# Oscilloscope.net
KiCad netlist of a schematic drawn in Altium Designer
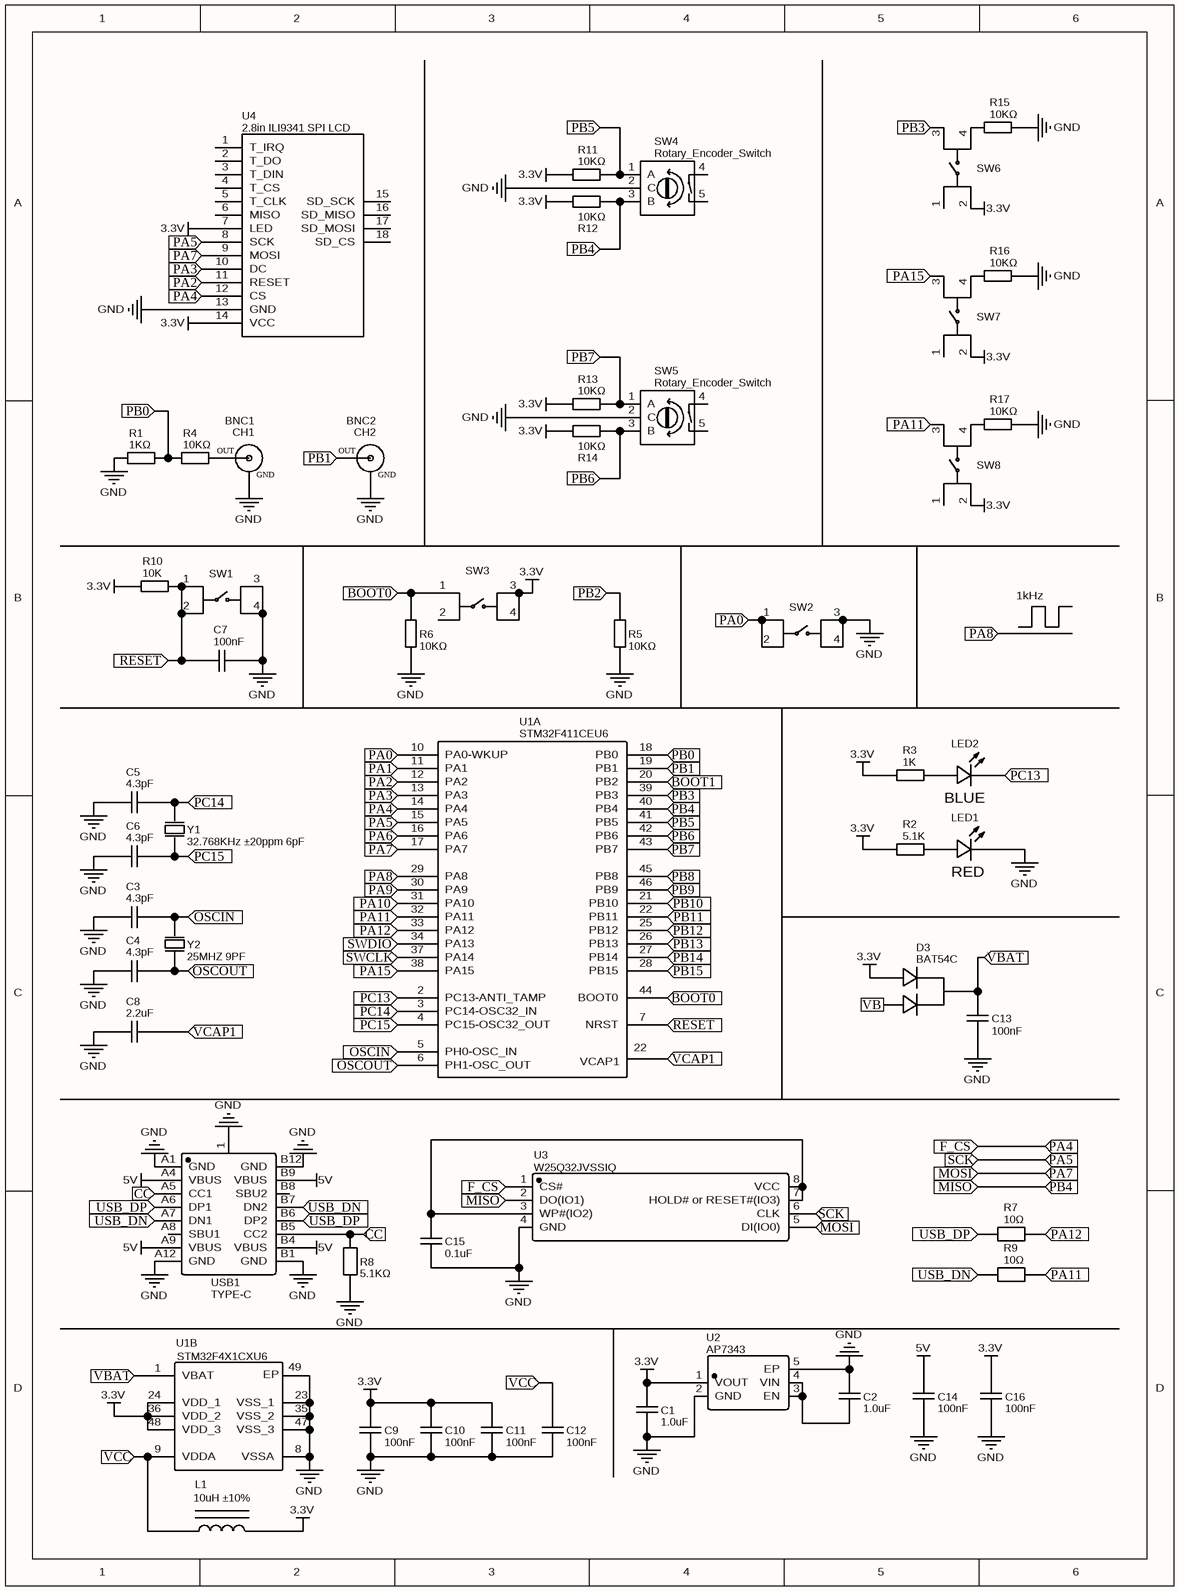
[diagram p0: Oscilloscope.schdoc]

(export (version "E")
  (design (tool "Eeschema 10.0.6"))
  (components
    (comp (ref "BNC1")
      (value "CH1")
      (fields (field (name "CONTRIBUTOR") "SparkFun"))
      (libsource (lib "altium-import") (part "root_0_CH1_"))
    )
    (comp (ref "BNC2")
      (value "CH2")
      (fields (field (name "CONTRIBUTOR") "SparkFun"))
      (libsource (lib "altium-import") (part "root_0_CH2_"))
    )
    (comp (ref "C1")
      (value "1.0uF")
      (fields (field (name "CONTRIBUTOR") "LCEDA_Lib"))
      (libsource (lib "altium-import") (part "root_3_1.0uF_"))
    )
    (comp (ref "C2")
      (value "1.0uF")
      (fields (field (name "CONTRIBUTOR") "LCEDA_Lib"))
      (libsource (lib "altium-import") (part "root_3_1.0uF_"))
    )
    (comp (ref "C3")
      (value "4.3pF")
      (fields (field (name "CONTRIBUTOR") "LCEDA_Lib"))
      (libsource (lib "altium-import") (part "root_0_4.3pF_"))
    )
    (comp (ref "C4")
      (value "4.3pF")
      (fields (field (name "CONTRIBUTOR") "LCEDA_Lib"))
      (libsource (lib "altium-import") (part "root_0_4.3pF_"))
    )
    (comp (ref "C5")
      (value "4.3pF")
      (fields (field (name "CONTRIBUTOR") "LCEDA_Lib"))
      (libsource (lib "altium-import") (part "root_0_4.3pF_"))
    )
    (comp (ref "C6")
      (value "4.3pF")
      (fields (field (name "CONTRIBUTOR") "LCEDA_Lib"))
      (libsource (lib "altium-import") (part "root_0_4.3pF_"))
    )
    (comp (ref "C7")
      (value "100nF")
      (fields (field (name "MANUFACTURER PART") "CL10A105KO8NNNC") (field (name "MANUFACTURER") "SAMSUNG"))
      (libsource (lib "altium-import") (part "root_0_100nF_"))
    )
    (comp (ref "C8")
      (value "2.2uF")
      (fields (field (name "CONTRIBUTOR") "LCEDA_Lib"))
      (libsource (lib "altium-import") (part "root_0_2.2uF_"))
    )
    (comp (ref "C9")
      (value "100nF")
      (fields (field (name "CONTRIBUTOR") "LCEDA_Lib"))
      (libsource (lib "altium-import") (part "root_3_100nF_"))
    )
    (comp (ref "C10")
      (value "100nF")
      (fields (field (name "CONTRIBUTOR") "LCEDA_Lib"))
      (libsource (lib "altium-import") (part "root_3_100nF_"))
    )
    (comp (ref "C11")
      (value "100nF")
      (fields (field (name "CONTRIBUTOR") "LCEDA_Lib"))
      (libsource (lib "altium-import") (part "root_3_100nF_"))
    )
    (comp (ref "C12")
      (value "100nF")
      (fields (field (name "CONTRIBUTOR") "LCEDA_Lib"))
      (libsource (lib "altium-import") (part "root_3_100nF_"))
    )
    (comp (ref "C13")
      (value "100nF")
      (fields (field (name "CONTRIBUTOR") "LCEDA_Lib"))
      (libsource (lib "altium-import") (part "root_3_100nF_"))
    )
    (comp (ref "C14")
      (value "100nF")
      (fields (field (name "CONTRIBUTOR") "LCEDA_Lib"))
      (libsource (lib "altium-import") (part "root_3_100nF_"))
    )
    (comp (ref "C15")
      (value "0.1uF")
      (fields (field (name "CONTRIBUTOR") "LCEDA_Lib"))
      (libsource (lib "altium-import") (part "root_3_0.1uF_"))
    )
    (comp (ref "C16")
      (value "100nF")
      (fields (field (name "CONTRIBUTOR") "LCEDA_Lib"))
      (libsource (lib "altium-import") (part "root_3_100nF_"))
    )
    (comp (ref "D3")
      (value "BAT54C")
      (fields (field (name "MANUFACTURER") "CJ(江苏长电/长晶)"))
      (libsource (lib "altium-import") (part "root_0_BAT54C_"))
    )
    (comp (ref "L1")
      (value "10uH ±10%")
      (fields (field (name "CONTRIBUTOR") "LCEDA_Lib"))
      (libsource (lib "altium-import") (part "root_0_10uH ±10%_"))
    )
    (comp (ref "LED1")
      (value "XL-0603QYGC")
      (fields (field (name "MANUFACTURER") "KENTO"))
      (libsource (lib "altium-import") (part "root_0_XL-0603QYGC_"))
    )
    (comp (ref "LED2")
      (value "XL-0603QYGC")
      (fields (field (name "MANUFACTURER") "KENTO"))
      (libsource (lib "altium-import") (part "root_0_XL-0603QYGC_"))
    )
    (comp (ref "R1")
      (value "1KΩ")
      (fields (field (name "MANUFACTURER") "YAGEO") (field (name "MANUFACTURER PART") "RC0603FR-07510RL"))
      (libsource (lib "altium-import") (part "root_0_1KΩ_"))
    )
    (comp (ref "R2")
      (value "5.1K")
      (fields (field (name "MANUFACTURER") "YAGEO") (field (name "MANUFACTURER PART") "RC0603FR-07510RL"))
      (libsource (lib "altium-import") (part "root_0_5.1K_"))
    )
    (comp (ref "R3")
      (value "1K")
      (fields (field (name "MANUFACTURER") "YAGEO") (field (name "MANUFACTURER PART") "RC0603FR-07510RL"))
      (libsource (lib "altium-import") (part "root_0_1K_"))
    )
    (comp (ref "R4")
      (value "10KΩ")
      (fields (field (name "MANUFACTURER") "YAGEO") (field (name "MANUFACTURER PART") "RC0603FR-07510RL"))
      (libsource (lib "altium-import") (part "root_0_10KΩ_"))
    )
    (comp (ref "R5")
      (value "10KΩ")
      (fields (field (name "MANUFACTURER") "YAGEO") (field (name "MANUFACTURER PART") "RC0603FR-07510RL"))
      (libsource (lib "altium-import") (part "root_1_10KΩ_"))
    )
    (comp (ref "R6")
      (value "10KΩ")
      (fields (field (name "MANUFACTURER") "YAGEO") (field (name "MANUFACTURER PART") "RC0603FR-07510RL"))
      (libsource (lib "altium-import") (part "root_1_10KΩ_"))
    )
    (comp (ref "R7")
      (value "10Ω")
      (fields (field (name "CONTRIBUTOR") "LCEDA_Lib"))
      (libsource (lib "altium-import") (part "root_0_10Ω_"))
    )
    (comp (ref "R8")
      (value "5.1KΩ")
      (fields (field (name "CONTRIBUTOR") "LCEDA_Lib"))
      (libsource (lib "altium-import") (part "root_3_5.1KΩ_"))
    )
    (comp (ref "R9")
      (value "10Ω")
      (fields (field (name "CONTRIBUTOR") "LCEDA_Lib"))
      (libsource (lib "altium-import") (part "root_0_10Ω_"))
    )
    (comp (ref "R10")
      (value "10K")
      (fields (field (name "MANUFACTURER") "YAGEO") (field (name "MANUFACTURER PART") "RC0603JR-0710KL"))
      (libsource (lib "altium-import") (part "root_2_10K_"))
    )
    (comp (ref "R11")
      (value "10KΩ")
      (fields (field (name "MANUFACTURER") "YAGEO") (field (name "MANUFACTURER PART") "RC0603FR-07510RL"))
      (libsource (lib "altium-import") (part "root_2_10KΩ_"))
    )
    (comp (ref "R12")
      (value "10KΩ")
      (fields (field (name "MANUFACTURER") "YAGEO") (field (name "MANUFACTURER PART") "RC0603FR-07510RL"))
      (libsource (lib "altium-import") (part "root_2_10KΩ_"))
    )
    (comp (ref "R13")
      (value "10KΩ")
      (fields (field (name "MANUFACTURER") "YAGEO") (field (name "MANUFACTURER PART") "RC0603FR-07510RL"))
      (libsource (lib "altium-import") (part "root_2_10KΩ_"))
    )
    (comp (ref "R14")
      (value "10KΩ")
      (fields (field (name "MANUFACTURER") "YAGEO") (field (name "MANUFACTURER PART") "RC0603FR-07510RL"))
      (libsource (lib "altium-import") (part "root_2_10KΩ_"))
    )
    (comp (ref "R15")
      (value "10KΩ")
      (fields (field (name "MANUFACTURER") "YAGEO") (field (name "MANUFACTURER PART") "RC0603FR-07510RL"))
      (libsource (lib "altium-import") (part "root_2_10KΩ_"))
    )
    (comp (ref "R16")
      (value "10KΩ")
      (fields (field (name "MANUFACTURER") "YAGEO") (field (name "MANUFACTURER PART") "RC0603FR-07510RL"))
      (libsource (lib "altium-import") (part "root_2_10KΩ_"))
    )
    (comp (ref "R17")
      (value "10KΩ")
      (fields (field (name "MANUFACTURER") "YAGEO") (field (name "MANUFACTURER PART") "RC0603FR-07510RL"))
      (libsource (lib "altium-import") (part "root_2_10KΩ_"))
    )
    (comp (ref "SW1")
      (value "K2-6639SP-C4SC-04")
      (fields (field (name "MANUFACTURER") "HRO"))
      (libsource (lib "altium-import") (part "root_0_K2-6639SP-C4SC-04_"))
    )
    (comp (ref "SW2")
      (value "K2-6639SP-C4SC-04")
      (fields (field (name "MANUFACTURER") "HRO"))
      (libsource (lib "altium-import") (part "root_0_K2-6639SP-C4SC-04_"))
    )
    (comp (ref "SW3")
      (value "K2-6639SP-C4SC-04")
      (fields (field (name "MANUFACTURER") "HRO"))
      (libsource (lib "altium-import") (part "root_0_K2-6639SP-C4SC-04_"))
    )
    (comp (ref "SW4")
      (value "Rotary_Encoder_Switch")
      (fields (field (name "CONTRIBUTOR") "vosemvosemsot"))
      (libsource (lib "altium-import") (part "root_0_Rotary_Encoder_Switch_"))
    )
    (comp (ref "SW5")
      (value "Rotary_Encoder_Switch")
      (fields (field (name "CONTRIBUTOR") "vosemvosemsot"))
      (libsource (lib "altium-import") (part "root_0_Rotary_Encoder_Switch_"))
    )
    (comp (ref "SW6")
      (value "K2-6639SP-C4SC-04")
      (fields (field (name "MANUFACTURER") "HRO"))
      (libsource (lib "altium-import") (part "root_1_K2-6639SP-C4SC-04_"))
    )
    (comp (ref "SW7")
      (value "K2-6639SP-C4SC-04")
      (fields (field (name "MANUFACTURER") "HRO"))
      (libsource (lib "altium-import") (part "root_1_K2-6639SP-C4SC-04_"))
    )
    (comp (ref "SW8")
      (value "K2-6639SP-C4SC-04")
      (fields (field (name "MANUFACTURER") "HRO"))
      (libsource (lib "altium-import") (part "root_1_K2-6639SP-C4SC-04_"))
    )
    (comp (ref "U1A")
      (value "STM32F411CEU6")
      (fields
        (field (name "MANUFACTURER") "ST")
        (field (name "MANUFACTURER PART") "STM32F103C8T6")
        (field (name "SUBPART_NO") "1")
      )
      (libsource (lib "altium-import") (part "root_0_STM32F411CEU6_"))
    )
    (comp (ref "U1B")
      (value "STM32F4X1CXU6")
      (fields
        (field (name "MANUFACTURER") "ST")
        (field (name "MANUFACTURER PART") "STM32F103C8T6")
        (field (name "SUBPART_NO") "2")
      )
      (libsource (lib "altium-import") (part "root_0_STM32F4X1CXU6_"))
    )
    (comp (ref "U2")
      (value "AP7343")
      (fields
        (field (name "MANUFACTURER") "DIODES(美台)")
        (field (name "MANUFACTURER PART") "AP7343D-22FS4-7B")
        (field (name "CONTRIBUTOR") "LCSC")
      )
      (libsource (lib "altium-import") (part "root_0_AP7343_"))
    )
    (comp (ref "U3")
      (value "W25Q32JVSSIQ")
      (fields (field (name "MANUFACTURER") "WINBOND(华邦)") (field (name "CONTRIBUTOR") "LCSC"))
      (libsource (lib "altium-import") (part "root_0_W25Q32JVSSIQ_"))
    )
    (comp (ref "U4")
      (value "2.8in ILI9341 SPI LCD")
      (fields (field (name "CONTRIBUTOR") "ananya0211"))
      (libsource (lib "altium-import") (part "root_0_2.8in ILI9341 SPI LCD_"))
    )
    (comp (ref "USB1")
      (value "TYPE-C")
      (fields
        (field (name "MANUFACTURER") "CIKI(皓富)")
        (field (name "MANUFACTURER PART") "TYPE-C-2.0-16PIN-SMT-3")
        (field (name "CONTRIBUTOR") "lcsc")
      )
      (libsource (lib "altium-import") (part "root_0_TYPE-C_"))
    )
    (comp (ref "Y1")
      (value "32.768KHz ±20ppm 6pF")
      (fields (field (name "MANUFACTURER") "YXC") (field (name "MANUFACTURER PART") "X49SD8MSD2SC"))
      (libsource (lib "altium-import") (part "root_1_32.768KHz ±20ppm 6pF_"))
    )
    (comp (ref "Y2")
      (value "25MHZ 9PF")
      (fields (field (name "MANUFACTURER") "YXC") (field (name "MANUFACTURER PART") "X49SD8MSD2SC"))
      (libsource (lib "altium-import") (part "root_1_25MHZ 9PF_"))
    )
  )
  (nets
    (net (code "1") (name "/BOOT0") (class "Default")
      (node (ref "R6") (pin "2") (pinfunction "2_2") (pintype "passive"))
      (node (ref "SW3") (pin "1") (pinfunction "1_1") (pintype "passive"))
      (node (ref "U1A") (pin "44") (pinfunction "BOOT0_44") (pintype "passive"))
    )
    (net (code "2") (name "/BOOT1") (class "Default")
      (node (ref "U1A") (pin "20") (pinfunction "PB2_20") (pintype "passive"))
    )
    (net (code "3") (name "/CC") (class "Default")
      (node (ref "R8") (pin "1") (pinfunction "1_1") (pintype "passive"))
      (node (ref "USB1") (pin "A5") (pinfunction "CC1_A5") (pintype "passive"))
      (node (ref "USB1") (pin "B5") (pinfunction "CC2_B5") (pintype "passive"))
    )
    (net (code "4") (name "/F_CS") (class "Default")
      (node (ref "U1A") (pin "14") (pinfunction "PA4_14") (pintype "passive"))
      (node (ref "U3") (pin "1") (pinfunction "CS#_1") (pintype "passive"))
      (node (ref "U4") (pin "12") (pinfunction "CS_12") (pintype "passive"))
    )
    (net (code "5") (name "/MISO") (class "Default")
      (node (ref "R12") (pin "1") (pinfunction "1_1") (pintype "passive"))
      (node (ref "SW4") (pin "3") (pinfunction "B_3") (pintype "passive"))
      (node (ref "U1A") (pin "40") (pinfunction "PB4_40") (pintype "passive"))
      (node (ref "U3") (pin "2") (pinfunction "DO(IO1)_2") (pintype "passive"))
    )
    (net (code "6") (name "/MOSI") (class "Default")
      (node (ref "U1A") (pin "17") (pinfunction "PA7_17") (pintype "passive"))
      (node (ref "U3") (pin "5") (pinfunction "DI(IO0)_5") (pintype "passive"))
      (node (ref "U4") (pin "9") (pinfunction "MOSI_9") (pintype "passive"))
    )
    (net (code "7") (name "/OSCIN") (class "Default")
      (node (ref "C3") (pin "2") (pinfunction "2_2") (pintype "passive"))
      (node (ref "U1A") (pin "5") (pinfunction "PH0-OSC_IN_5") (pintype "passive"))
      (node (ref "Y2") (pin "1") (pinfunction "OSC1_1") (pintype "passive"))
    )
    (net (code "8") (name "/OSCOUT") (class "Default")
      (node (ref "C4") (pin "2") (pinfunction "2_2") (pintype "passive"))
      (node (ref "U1A") (pin "6") (pinfunction "PH1-OSC_OUT_6") (pintype "passive"))
      (node (ref "Y2") (pin "2") (pinfunction "OSC2_2") (pintype "passive"))
    )
    (net (code "9") (name "/PA0") (class "Default")
      (node (ref "SW2") (pin "1") (pinfunction "1_1") (pintype "passive"))
      (node (ref "SW2") (pin "2") (pinfunction "2_2") (pintype "passive"))
      (node (ref "U1A") (pin "10") (pinfunction "PA0-WKUP_10") (pintype "passive"))
    )
    (net (code "10") (name "/PA1") (class "Default")
      (node (ref "U1A") (pin "11") (pinfunction "PA1_11") (pintype "passive"))
    )
    (net (code "11") (name "/PA2") (class "Default")
      (node (ref "U1A") (pin "12") (pinfunction "PA2_12") (pintype "passive"))
      (node (ref "U4") (pin "11") (pinfunction "RESET_11") (pintype "passive"))
    )
    (net (code "12") (name "/PA3") (class "Default")
      (node (ref "U1A") (pin "13") (pinfunction "PA3_13") (pintype "passive"))
      (node (ref "U4") (pin "10") (pinfunction "DC_10") (pintype "passive"))
    )
    (net (code "13") (name "/PA5") (class "Default")
      (node (ref "U1A") (pin "15") (pinfunction "PA5_15") (pintype "passive"))
      (node (ref "U3") (pin "6") (pinfunction "CLK_6") (pintype "passive"))
      (node (ref "U4") (pin "8") (pinfunction "SCK_8") (pintype "passive"))
    )
    (net (code "14") (name "/PA6") (class "Default")
      (node (ref "U1A") (pin "16") (pinfunction "PA6_16") (pintype "passive"))
    )
    (net (code "15") (name "/PA8") (class "Default")
      (node (ref "U1A") (pin "29") (pinfunction "PA8_29") (pintype "passive"))
    )
    (net (code "16") (name "/PA9") (class "Default")
      (node (ref "U1A") (pin "30") (pinfunction "PA9_30") (pintype "passive"))
    )
    (net (code "17") (name "/PA10") (class "Default")
      (node (ref "U1A") (pin "31") (pinfunction "PA10_31") (pintype "passive"))
    )
    (net (code "18") (name "/PA11") (class "Default")
      (node (ref "R9") (pin "2") (pinfunction "2_2") (pintype "passive"))
      (node (ref "SW8") (pin "3") (pinfunction "3_3") (pintype "passive"))
      (node (ref "U1A") (pin "32") (pinfunction "PA11_32") (pintype "passive"))
    )
    (net (code "19") (name "/PA12") (class "Default")
      (node (ref "R7") (pin "2") (pinfunction "2_2") (pintype "passive"))
      (node (ref "U1A") (pin "33") (pinfunction "PA12_33") (pintype "passive"))
    )
    (net (code "20") (name "/PA15") (class "Default")
      (node (ref "SW7") (pin "3") (pinfunction "3_3") (pintype "passive"))
      (node (ref "U1A") (pin "38") (pinfunction "PA15_38") (pintype "passive"))
    )
    (net (code "21") (name "/PB0") (class "Default")
      (node (ref "R1") (pin "2") (pinfunction "2_2") (pintype "passive"))
      (node (ref "R4") (pin "1") (pinfunction "1_1") (pintype "passive"))
      (node (ref "U1A") (pin "18") (pinfunction "PB0_18") (pintype "passive"))
    )
    (net (code "22") (name "/PB1") (class "Default")
      (node (ref "BNC2") (pin "S") (pinfunction "OUT_S") (pintype "passive"))
      (node (ref "U1A") (pin "19") (pinfunction "PB1_19") (pintype "passive"))
    )
    (net (code "23") (name "/PB2") (class "Default")
      (node (ref "R5") (pin "2") (pinfunction "2_2") (pintype "passive"))
    )
    (net (code "24") (name "/PB3") (class "Default")
      (node (ref "SW6") (pin "3") (pinfunction "3_3") (pintype "passive"))
      (node (ref "U1A") (pin "39") (pinfunction "PB3_39") (pintype "passive"))
    )
    (net (code "25") (name "/PB5") (class "Default")
      (node (ref "R11") (pin "1") (pinfunction "1_1") (pintype "passive"))
      (node (ref "SW4") (pin "1") (pinfunction "A_1") (pintype "passive"))
      (node (ref "U1A") (pin "41") (pinfunction "PB5_41") (pintype "passive"))
    )
    (net (code "26") (name "/PB6") (class "Default")
      (node (ref "R14") (pin "1") (pinfunction "1_1") (pintype "passive"))
      (node (ref "SW5") (pin "3") (pinfunction "B_3") (pintype "passive"))
      (node (ref "U1A") (pin "42") (pinfunction "PB6_42") (pintype "passive"))
    )
    (net (code "27") (name "/PB7") (class "Default")
      (node (ref "R13") (pin "1") (pinfunction "1_1") (pintype "passive"))
      (node (ref "SW5") (pin "1") (pinfunction "A_1") (pintype "passive"))
      (node (ref "U1A") (pin "43") (pinfunction "PB7_43") (pintype "passive"))
    )
    (net (code "28") (name "/PB8") (class "Default")
      (node (ref "U1A") (pin "45") (pinfunction "PB8_45") (pintype "passive"))
    )
    (net (code "29") (name "/PB9") (class "Default")
      (node (ref "U1A") (pin "46") (pinfunction "PB9_46") (pintype "passive"))
    )
    (net (code "30") (name "/PB10") (class "Default")
      (node (ref "U1A") (pin "21") (pinfunction "PB10_21") (pintype "passive"))
    )
    (net (code "31") (name "/PB11") (class "Default")
      (node (ref "U1A") (pin "22") (pinfunction "PB11_22") (pintype "passive"))
    )
    (net (code "32") (name "/PB12") (class "Default")
      (node (ref "U1A") (pin "25") (pinfunction "PB12_25") (pintype "passive"))
    )
    (net (code "33") (name "/PB13") (class "Default")
      (node (ref "U1A") (pin "26") (pinfunction "PB13_26") (pintype "passive"))
    )
    (net (code "34") (name "/PB14") (class "Default")
      (node (ref "U1A") (pin "27") (pinfunction "PB14_27") (pintype "passive"))
    )
    (net (code "35") (name "/PB15") (class "Default")
      (node (ref "U1A") (pin "28") (pinfunction "PB15_28") (pintype "passive"))
    )
    (net (code "36") (name "/PC13") (class "Default")
      (node (ref "LED2") (pin "2") (pinfunction "K_2") (pintype "passive"))
      (node (ref "U1A") (pin "2") (pinfunction "PC13-ANTI_TAMP_2") (pintype "passive"))
    )
    (net (code "37") (name "/PC14") (class "Default")
      (node (ref "C5") (pin "2") (pinfunction "2_2") (pintype "passive"))
      (node (ref "U1A") (pin "3") (pinfunction "PC14-OSC32_IN_3") (pintype "passive"))
      (node (ref "Y1") (pin "1") (pinfunction "OSC1_1") (pintype "passive"))
    )
    (net (code "38") (name "/PC15") (class "Default")
      (node (ref "C6") (pin "2") (pinfunction "2_2") (pintype "passive"))
      (node (ref "U1A") (pin "4") (pinfunction "PC15-OSC32_OUT_4") (pintype "passive"))
      (node (ref "Y1") (pin "2") (pinfunction "OSC2_2") (pintype "passive"))
    )
    (net (code "39") (name "/RESET") (class "Default")
      (node (ref "C7") (pin "1") (pinfunction "1_1") (pintype "passive"))
      (node (ref "R10") (pin "1") (pinfunction "1_1") (pintype "passive"))
      (node (ref "SW1") (pin "1") (pinfunction "1_1") (pintype "passive"))
      (node (ref "SW1") (pin "2") (pinfunction "2_2") (pintype "passive"))
      (node (ref "U1A") (pin "7") (pinfunction "NRST_7") (pintype "passive"))
    )
    (net (code "40") (name "/SWCLK") (class "Default")
      (node (ref "U1A") (pin "37") (pinfunction "PA14_37") (pintype "passive"))
    )
    (net (code "41") (name "/SWDIO") (class "Default")
      (node (ref "U1A") (pin "34") (pinfunction "PA13_34") (pintype "passive"))
    )
    (net (code "42") (name "/USB_DN") (class "Default")
      (node (ref "R9") (pin "1") (pinfunction "1_1") (pintype "passive"))
      (node (ref "USB1") (pin "A7") (pinfunction "DN1_A7") (pintype "passive"))
      (node (ref "USB1") (pin "B7") (pinfunction "DN2_B7") (pintype "passive"))
    )
    (net (code "43") (name "/USB_DP") (class "Default")
      (node (ref "R7") (pin "1") (pinfunction "1_1") (pintype "passive"))
      (node (ref "USB1") (pin "A6") (pinfunction "DP1_A6") (pintype "passive"))
      (node (ref "USB1") (pin "B6") (pinfunction "DP2_B6") (pintype "passive"))
    )
    (net (code "44") (name "/VB") (class "Default")
      (node (ref "D3") (pin "2") (pinfunction "A2_2") (pintype "passive"))
    )
    (net (code "45") (name "/VBAT") (class "Default")
      (node (ref "C13") (pin "1") (pinfunction "1_1") (pintype "passive"))
      (node (ref "D3") (pin "3") (pinfunction "K_3") (pintype "passive"))
      (node (ref "U1B") (pin "1") (pinfunction "VBAT_1") (pintype "passive"))
    )
    (net (code "46") (name "/VCAP1") (class "Default")
      (node (ref "C8") (pin "2") (pinfunction "2_2") (pintype "passive"))
    )
    (net (code "47") (name "/VCC") (class "Default")
      (node (ref "C12") (pin "1") (pinfunction "1_1") (pintype "passive"))
      (node (ref "L1") (pin "1") (pinfunction "1_1") (pintype "passive"))
      (node (ref "U1B") (pin "9") (pinfunction "VDDA_9") (pintype "passive"))
    )
    (net (code "48") (name "3.3V") (class "Default")
      (node (ref "C1") (pin "1") (pinfunction "1_1") (pintype "passive"))
      (node (ref "C10") (pin "1") (pinfunction "1_1") (pintype "passive"))
      (node (ref "C11") (pin "1") (pinfunction "1_1") (pintype "passive"))
      (node (ref "C16") (pin "1") (pinfunction "1_1") (pintype "passive"))
      (node (ref "C9") (pin "1") (pinfunction "1_1") (pintype "passive"))
      (node (ref "D3") (pin "1") (pinfunction "A1_1") (pintype "passive"))
      (node (ref "L1") (pin "2") (pinfunction "2_2") (pintype "passive"))
      (node (ref "R10") (pin "2") (pinfunction "2_2") (pintype "passive"))
      (node (ref "R11") (pin "2") (pinfunction "2_2") (pintype "passive"))
      (node (ref "R12") (pin "2") (pinfunction "2_2") (pintype "passive"))
      (node (ref "R13") (pin "2") (pinfunction "2_2") (pintype "passive"))
      (node (ref "R14") (pin "2") (pinfunction "2_2") (pintype "passive"))
      (node (ref "R2") (pin "1") (pinfunction "1_1") (pintype "passive"))
      (node (ref "R3") (pin "1") (pinfunction "1_1") (pintype "passive"))
      (node (ref "SW3") (pin "3") (pinfunction "3_3") (pintype "passive"))
      (node (ref "SW3") (pin "4") (pinfunction "4_4") (pintype "passive"))
      (node (ref "SW6") (pin "2") (pinfunction "2_2") (pintype "passive"))
      (node (ref "SW7") (pin "2") (pinfunction "2_2") (pintype "passive"))
      (node (ref "SW8") (pin "2") (pinfunction "2_2") (pintype "passive"))
      (node (ref "U1B") (pin "24") (pinfunction "VDD_1_24") (pintype "passive"))
      (node (ref "U1B") (pin "36") (pinfunction "VDD_2_36") (pintype "passive"))
      (node (ref "U1B") (pin "48") (pinfunction "VDD_3_48") (pintype "passive"))
      (node (ref "U2") (pin "1") (pinfunction "VOUT_1") (pintype "passive"))
      (node (ref "U4") (pin "14") (pinfunction "VCC_14") (pintype "passive"))
      (node (ref "U4") (pin "7") (pinfunction "LED_7") (pintype "passive"))
    )
    (net (code "49") (name "5V") (class "Default")
      (node (ref "C14") (pin "1") (pinfunction "1_1") (pintype "passive"))
      (node (ref "USB1") (pin "A4") (pinfunction "VBUS_A4") (pintype "passive"))
      (node (ref "USB1") (pin "A9") (pinfunction "VBUS_A9") (pintype "passive"))
      (node (ref "USB1") (pin "B4") (pinfunction "VBUS_B4") (pintype "passive"))
      (node (ref "USB1") (pin "B9") (pinfunction "VBUS_B9") (pintype "passive"))
    )
    (net (code "50") (name "GND") (class "Default")
      (node (ref "BNC1") (pin "GND") (pinfunction "GND_GND") (pintype "passive"))
      (node (ref "BNC2") (pin "GND") (pinfunction "GND_GND") (pintype "passive"))
      (node (ref "C1") (pin "2") (pinfunction "2_2") (pintype "passive"))
      (node (ref "C10") (pin "2") (pinfunction "2_2") (pintype "passive"))
      (node (ref "C11") (pin "2") (pinfunction "2_2") (pintype "passive"))
      (node (ref "C12") (pin "2") (pinfunction "2_2") (pintype "passive"))
      (node (ref "C13") (pin "2") (pinfunction "2_2") (pintype "passive"))
      (node (ref "C14") (pin "2") (pinfunction "2_2") (pintype "passive"))
      (node (ref "C15") (pin "2") (pinfunction "2_2") (pintype "passive"))
      (node (ref "C16") (pin "2") (pinfunction "2_2") (pintype "passive"))
      (node (ref "C2") (pin "1") (pinfunction "1_1") (pintype "passive"))
      (node (ref "C3") (pin "1") (pinfunction "1_1") (pintype "passive"))
      (node (ref "C4") (pin "1") (pinfunction "1_1") (pintype "passive"))
      (node (ref "C5") (pin "1") (pinfunction "1_1") (pintype "passive"))
      (node (ref "C6") (pin "1") (pinfunction "1_1") (pintype "passive"))
      (node (ref "C7") (pin "2") (pinfunction "2_2") (pintype "passive"))
      (node (ref "C8") (pin "1") (pinfunction "1_1") (pintype "passive"))
      (node (ref "C9") (pin "2") (pinfunction "2_2") (pintype "passive"))
      (node (ref "LED1") (pin "2") (pinfunction "K_2") (pintype "passive"))
      (node (ref "R1") (pin "1") (pinfunction "1_1") (pintype "passive"))
      (node (ref "R15") (pin "1") (pinfunction "1_1") (pintype "passive"))
      (node (ref "R16") (pin "1") (pinfunction "1_1") (pintype "passive"))
      (node (ref "R17") (pin "1") (pinfunction "1_1") (pintype "passive"))
      (node (ref "R5") (pin "1") (pinfunction "1_1") (pintype "passive"))
      (node (ref "R6") (pin "1") (pinfunction "1_1") (pintype "passive"))
      (node (ref "R8") (pin "2") (pinfunction "2_2") (pintype "passive"))
      (node (ref "SW1") (pin "3") (pinfunction "3_3") (pintype "passive"))
      (node (ref "SW1") (pin "4") (pinfunction "4_4") (pintype "passive"))
      (node (ref "SW2") (pin "3") (pinfunction "3_3") (pintype "passive"))
      (node (ref "SW2") (pin "4") (pinfunction "4_4") (pintype "passive"))
      (node (ref "SW4") (pin "2") (pinfunction "C_2") (pintype "passive"))
      (node (ref "SW5") (pin "2") (pinfunction "C_2") (pintype "passive"))
      (node (ref "U1B") (pin "23") (pinfunction "VSS_1_23") (pintype "passive"))
      (node (ref "U1B") (pin "35") (pinfunction "VSS_2_35") (pintype "passive"))
      (node (ref "U1B") (pin "47") (pinfunction "VSS_3_47") (pintype "passive"))
      (node (ref "U1B") (pin "8") (pinfunction "VSSA_8") (pintype "passive"))
      (node (ref "U2") (pin "2") (pinfunction "GND_2") (pintype "passive"))
      (node (ref "U2") (pin "5") (pinfunction "EP_5") (pintype "passive"))
      (node (ref "U3") (pin "4") (pinfunction "GND_4") (pintype "passive"))
      (node (ref "U4") (pin "13") (pinfunction "GND_13") (pintype "passive"))
      (node (ref "USB1") (pin "1") (pinfunction "EH_1") (pintype "passive"))
      (node (ref "USB1") (pin "A1") (pinfunction "GND_A1") (pintype "passive"))
      (node (ref "USB1") (pin "A12") (pinfunction "GND_A12") (pintype "passive"))
      (node (ref "USB1") (pin "B1") (pinfunction "GND_B1") (pintype "passive"))
      (node (ref "USB1") (pin "B12") (pinfunction "GND_B12") (pintype "passive"))
    )
    (net (code "51") (name "Net-(BNC1-OUT)") (class "Default")
      (node (ref "BNC1") (pin "S") (pinfunction "OUT_S") (pintype "passive"))
      (node (ref "R4") (pin "2") (pinfunction "2_2") (pintype "passive"))
    )
    (net (code "52") (name "Net-(LED1-A)") (class "Default")
      (node (ref "LED1") (pin "1") (pinfunction "A_1") (pintype "passive"))
      (node (ref "R2") (pin "2") (pinfunction "2_2") (pintype "passive"))
    )
    (net (code "53") (name "Net-(LED2-A)") (class "Default")
      (node (ref "LED2") (pin "1") (pinfunction "A_1") (pintype "passive"))
      (node (ref "R3") (pin "2") (pinfunction "2_2") (pintype "passive"))
    )
    (net (code "54") (name "Net-(R15-Pad2)") (class "Default")
      (node (ref "R15") (pin "2") (pinfunction "2_2") (pintype "passive"))
      (node (ref "SW6") (pin "4") (pinfunction "4_4") (pintype "passive"))
    )
    (net (code "55") (name "Net-(R16-Pad2)") (class "Default")
      (node (ref "R16") (pin "2") (pinfunction "2_2") (pintype "passive"))
      (node (ref "SW7") (pin "4") (pinfunction "4_4") (pintype "passive"))
    )
    (net (code "56") (name "Net-(R17-Pad2)") (class "Default")
      (node (ref "R17") (pin "2") (pinfunction "2_2") (pintype "passive"))
      (node (ref "SW8") (pin "4") (pinfunction "4_4") (pintype "passive"))
    )
    (net (code "57") (name "Net-(U2-EN)") (class "Default")
      (node (ref "C2") (pin "2") (pinfunction "2_2") (pintype "passive"))
      (node (ref "U2") (pin "3") (pinfunction "EN_3") (pintype "passive"))
      (node (ref "U2") (pin "4") (pinfunction "VIN_4") (pintype "passive"))
    )
    (net (code "58") (name "Net-(U3-HOLD#_or_RESET#(IO3))") (class "Default")
      (node (ref "C15") (pin "1") (pinfunction "1_1") (pintype "passive"))
      (node (ref "U3") (pin "3") (pinfunction "WP#(IO2)_3") (pintype "passive"))
      (node (ref "U3") (pin "7") (pinfunction "HOLD#_or_RESET#(IO3)_7") (pintype "passive"))
      (node (ref "U3") (pin "8") (pinfunction "VCC_8") (pintype "passive"))
    )
    (net (code "59") (name "unconnected-(SW3-Pad2)") (class "Default")
      (node (ref "SW3") (pin "2") (pinfunction "2_2") (pintype "passive"))
    )
    (net (code "60") (name "unconnected-(SW4-Pad4)") (class "Default")
      (node (ref "SW4") (pin "4") (pintype "passive"))
    )
    (net (code "61") (name "unconnected-(SW4-Pad5)") (class "Default")
      (node (ref "SW4") (pin "5") (pintype "passive"))
    )
    (net (code "62") (name "unconnected-(SW5-Pad4)") (class "Default")
      (node (ref "SW5") (pin "4") (pintype "passive"))
    )
    (net (code "63") (name "unconnected-(SW5-Pad5)") (class "Default")
      (node (ref "SW5") (pin "5") (pintype "passive"))
    )
    (net (code "64") (name "unconnected-(SW6-Pad1)") (class "Default")
      (node (ref "SW6") (pin "1") (pinfunction "1_1") (pintype "passive"))
    )
    (net (code "65") (name "unconnected-(SW7-Pad1)") (class "Default")
      (node (ref "SW7") (pin "1") (pinfunction "1_1") (pintype "passive"))
    )
    (net (code "66") (name "unconnected-(SW8-Pad1)") (class "Default")
      (node (ref "SW8") (pin "1") (pinfunction "1_1") (pintype "passive"))
    )
    (net (code "67") (name "unconnected-(U4-MISO-Pad6)") (class "Default")
      (node (ref "U4") (pin "6") (pinfunction "MISO_6") (pintype "passive"))
    )
    (net (code "68") (name "unconnected-(U4-SD_CS-Pad18)") (class "Default")
      (node (ref "U4") (pin "18") (pinfunction "SD_CS_18") (pintype "passive"))
    )
    (net (code "69") (name "unconnected-(U4-SD_MISO-Pad16)") (class "Default")
      (node (ref "U4") (pin "16") (pinfunction "SD_MISO_16") (pintype "passive"))
    )
    (net (code "70") (name "unconnected-(U4-SD_MOSI-Pad17)") (class "Default")
      (node (ref "U4") (pin "17") (pinfunction "SD_MOSI_17") (pintype "passive"))
    )
    (net (code "71") (name "unconnected-(U4-SD_SCK-Pad15)") (class "Default")
      (node (ref "U4") (pin "15") (pinfunction "SD_SCK_15") (pintype "passive"))
    )
    (net (code "72") (name "unconnected-(U4-T_CLK-Pad5)") (class "Default")
      (node (ref "U4") (pin "5") (pinfunction "T_CLK_5") (pintype "passive"))
    )
    (net (code "73") (name "unconnected-(U4-T_CS-Pad4)") (class "Default")
      (node (ref "U4") (pin "4") (pinfunction "T_CS_4") (pintype "passive"))
    )
    (net (code "74") (name "unconnected-(U4-T_DIN-Pad3)") (class "Default")
      (node (ref "U4") (pin "3") (pinfunction "T_DIN_3") (pintype "passive"))
    )
    (net (code "75") (name "unconnected-(U4-T_DO-Pad2)") (class "Default")
      (node (ref "U4") (pin "2") (pinfunction "T_DO_2") (pintype "passive"))
    )
    (net (code "76") (name "unconnected-(U4-T_IRQ-Pad1)") (class "Default")
      (node (ref "U4") (pin "1") (pinfunction "T_IRQ_1") (pintype "passive"))
    )
    (net (code "77") (name "unconnected-(USB1-SBU1-PadA8)") (class "Default")
      (node (ref "USB1") (pin "A8") (pinfunction "SBU1_A8") (pintype "passive"))
    )
    (net (code "78") (name "unconnected-(USB1-SBU2-PadB8)") (class "Default")
      (node (ref "USB1") (pin "B8") (pinfunction "SBU2_B8") (pintype "passive"))
    )
  )
)
